# paste_injector.net
KiCad netlist of a schematic drawn in EAGLE
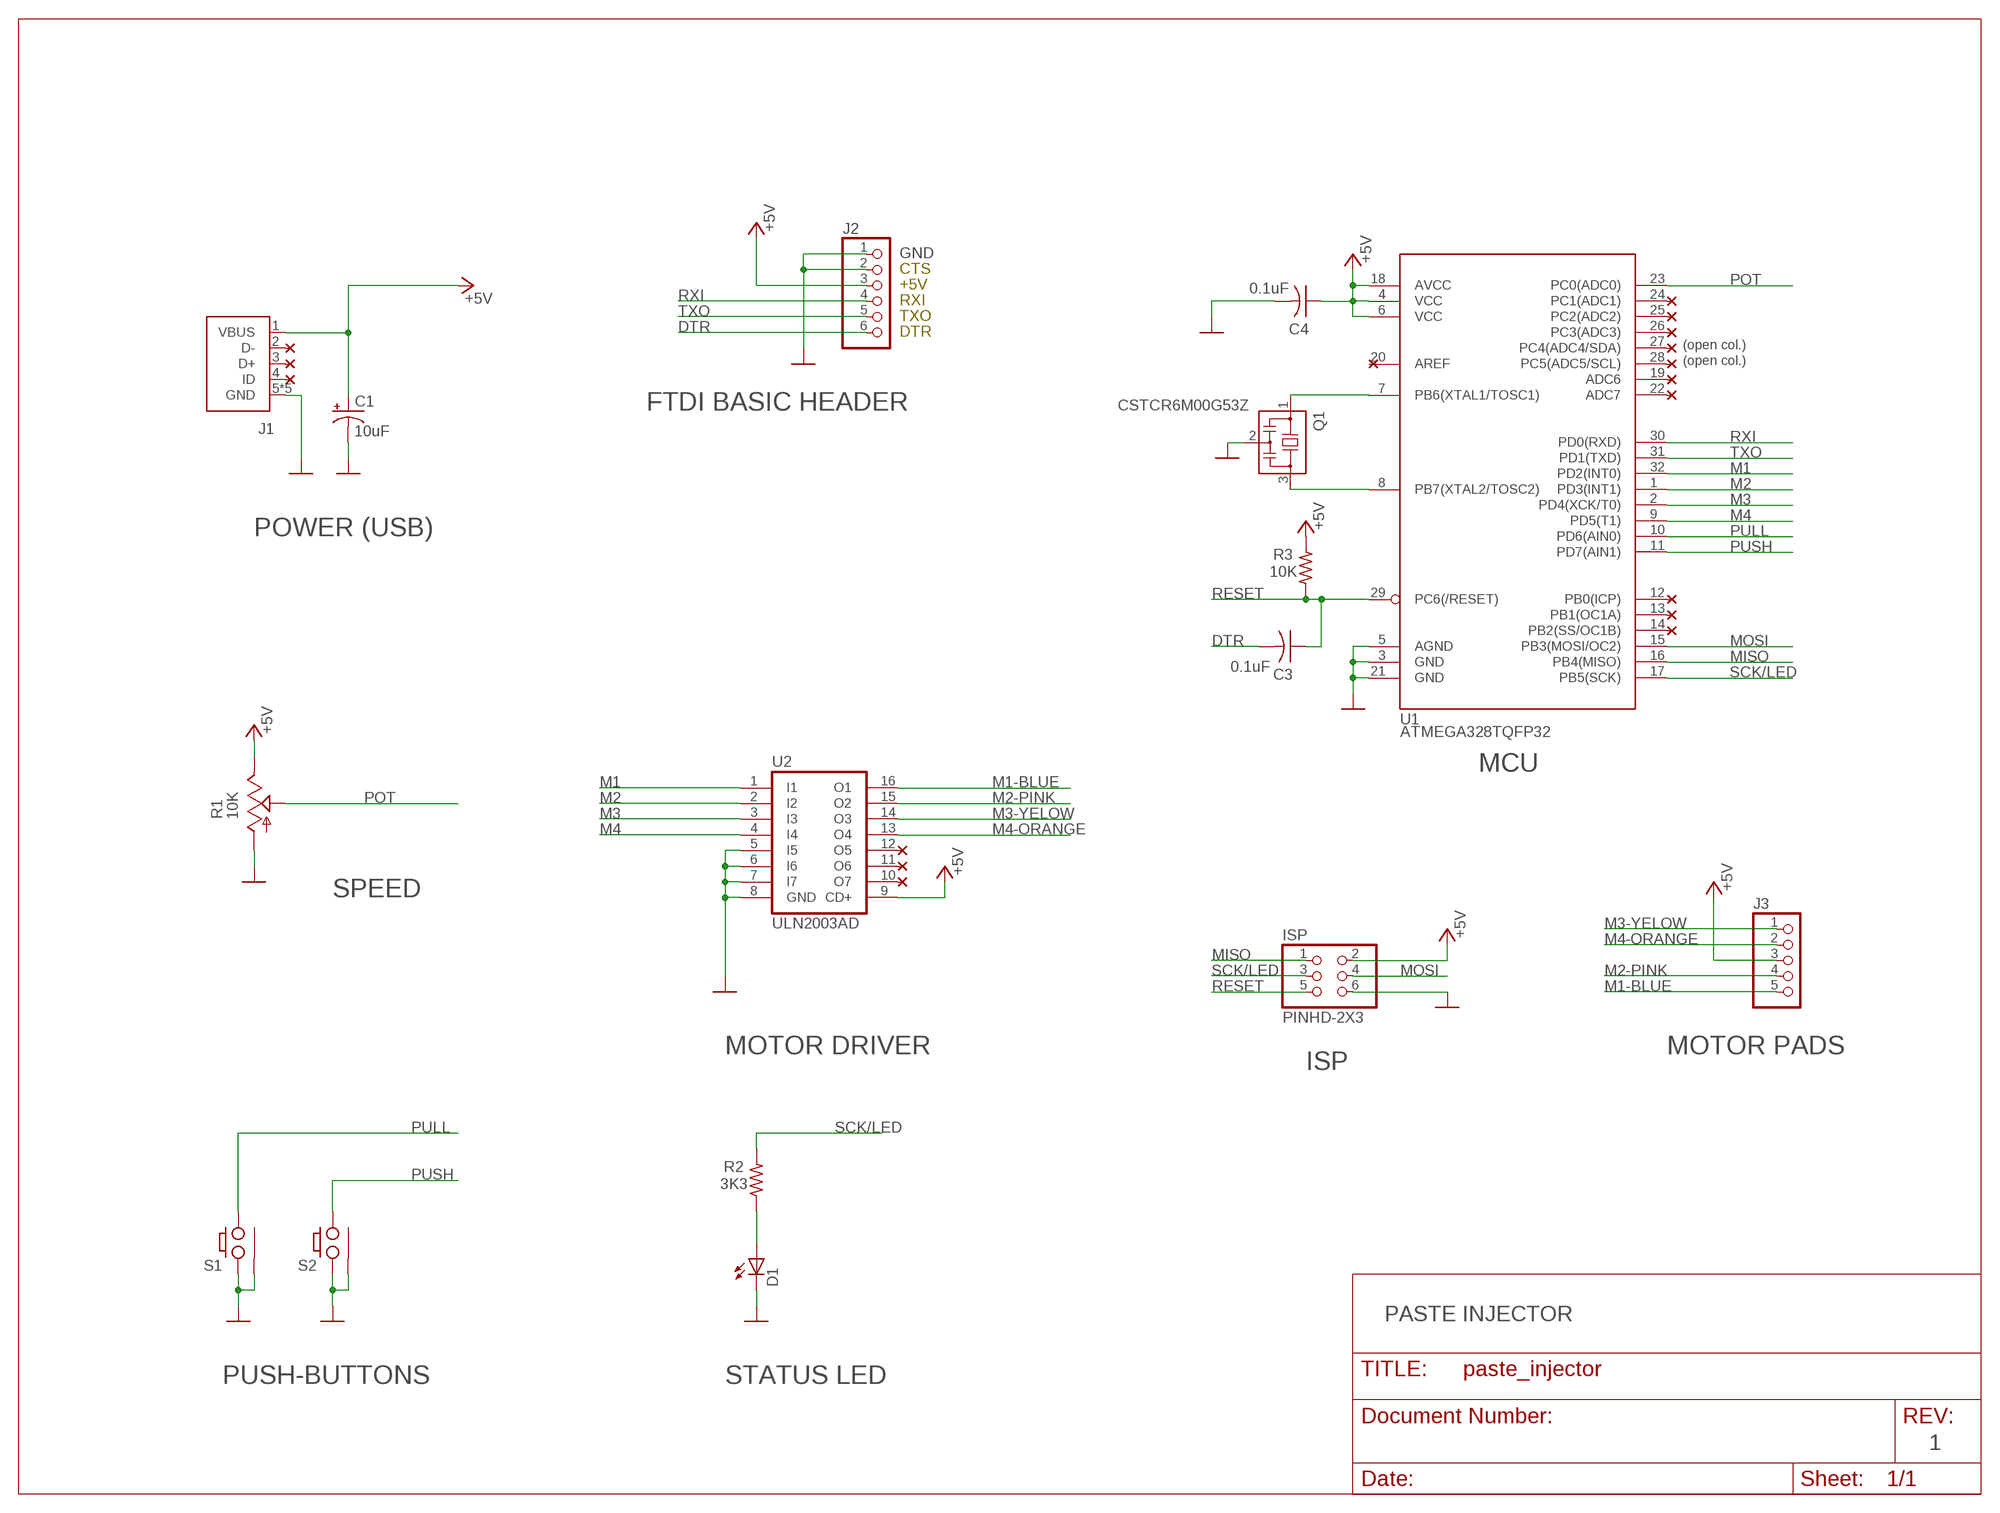
[diagram p0: schematic, sheet 1]

(export (version "E")
  (design (tool "Eeschema 10.0.6"))
  (components
    (comp (ref "C1")
      (value "10uF")
      (footprint "eagle-import:A_3216-18R")
      (libsource (lib "eagle-import") (part "CPOL-USA/3216-18R"))
    )
    (comp (ref "C3")
      (value "0.1uF")
      (footprint "eagle-import:C0603")
      (libsource (lib "eagle-import") (part "CAP-C0603"))
    )
    (comp (ref "C4")
      (value "0.1uF")
      (footprint "eagle-import:C0603")
      (libsource (lib "eagle-import") (part "CAP-C0603"))
    )
    (comp (ref "D1")
      (value "LED")
      (footprint "eagle-import:LED0603")
      (libsource (lib "eagle-import") (part "LED"))
    )
    (comp (ref "ISP")
      (value "PINHD-2X3")
      (footprint "eagle-import:2X03")
      (libsource (lib "eagle-import") (part "PINHD-2X3"))
    )
    (comp (ref "J1")
      (value "USB")
      (footprint "eagle-import:USB-MICRO-ZX62RD-AB-5P8")
      (libsource (lib "eagle-import") (part "USB"))
    )
    (comp (ref "J2")
      (value "PINHD-1X6")
      (footprint "eagle-import:1X06")
      (libsource (lib "eagle-import") (part "PINHD-1X6"))
    )
    (comp (ref "J3")
      (value "PINHD-1X5")
      (footprint "eagle-import:1X05")
      (libsource (lib "eagle-import") (part "PINHD-1X5"))
    )
    (comp (ref "Q1")
      (value "CSTCR6M00G53Z")
      (footprint "eagle-import:CSTCR6M")
      (fields (field (name "MPN") "CSTCR6M00G53-R0"))
      (libsource (lib "eagle-import") (part "CSTCR6M00G53Z"))
    )
    (comp (ref "R1")
      (value "10K")
      (footprint "eagle-import:TRIMPOT")
      (libsource (lib "eagle-import") (part "TRIMPOTCA9V"))
    )
    (comp (ref "R2")
      (value "3K3")
      (footprint "eagle-import:R0603")
      (libsource (lib "eagle-import") (part "RES-R0603"))
    )
    (comp (ref "R3")
      (value "10K")
      (footprint "eagle-import:R0603")
      (libsource (lib "eagle-import") (part "RES-R0603"))
    )
    (comp (ref "S1")
      (value "PUSH_BUTTON")
      (footprint "eagle-import:PUSH_BUTTON")
      (libsource (lib "eagle-import") (part "PUSH_BUTTON"))
    )
    (comp (ref "S2")
      (value "PUSH_BUTTON")
      (footprint "eagle-import:PUSH_BUTTON")
      (libsource (lib "eagle-import") (part "PUSH_BUTTON"))
    )
    (comp (ref "U1")
      (value "ATMEGA328TQFP32")
      (footprint "eagle-import:TQFP32-08")
      (libsource (lib "eagle-import") (part "ATMEGA328TQFP32"))
    )
    (comp (ref "U2")
      (value "ULN2003AD")
      (footprint "eagle-import:SO16")
      (libsource (lib "eagle-import") (part "ULN2003AD"))
    )
  )
  (nets
    (net (code "1") (name "+5V") (class "Default")
      (node (ref "C1") (pin "+") (pinfunction "+_+") (pintype "passive"))
      (node (ref "C4") (pin "1") (pinfunction "1_1") (pintype "passive"))
      (node (ref "ISP") (pin "2") (pinfunction "2_2") (pintype "passive"))
      (node (ref "J1") (pin "1") (pinfunction "VBUS_1") (pintype "bidirectional"))
      (node (ref "J2") (pin "3") (pinfunction "3_3") (pintype "passive"))
      (node (ref "J3") (pin "3") (pinfunction "3_3") (pintype "passive"))
      (node (ref "R1") (pin "CW") (pinfunction "CW_CW") (pintype "passive"))
      (node (ref "R3") (pin "2") (pinfunction "2_2") (pintype "passive"))
      (node (ref "U1") (pin "18") (pinfunction "AVCC_18") (pintype "power_in"))
      (node (ref "U1") (pin "4") (pinfunction "VCC_4") (pintype "power_in"))
      (node (ref "U1") (pin "6") (pinfunction "VCC_6") (pintype "power_in"))
      (node (ref "U2") (pin "9") (pinfunction "CD+_9") (pintype "passive"))
    )
    (net (code "2") (name "/AREF") (class "Default")
      (node (ref "U1") (pin "20") (pinfunction "AREF_20") (pintype "power_in"))
    )
    (net (code "3") (name "/DTR") (class "Default")
      (node (ref "C3") (pin "2") (pinfunction "2_2") (pintype "passive"))
      (node (ref "J2") (pin "6") (pinfunction "6_6") (pintype "passive"))
    )
    (net (code "4") (name "/M1") (class "Default")
      (node (ref "U1") (pin "32") (pinfunction "PD2(INT0)_32") (pintype "bidirectional"))
      (node (ref "U2") (pin "1") (pinfunction "I1_1") (pintype "input"))
    )
    (net (code "5") (name "/M1-BLUE") (class "Default")
      (node (ref "J3") (pin "5") (pinfunction "5_5") (pintype "passive"))
      (node (ref "U2") (pin "16") (pinfunction "O1_16") (pintype "open_collector"))
    )
    (net (code "6") (name "/M2") (class "Default")
      (node (ref "U1") (pin "1") (pinfunction "PD3(INT1)_1") (pintype "bidirectional"))
      (node (ref "U2") (pin "2") (pinfunction "I2_2") (pintype "input"))
    )
    (net (code "7") (name "/M2-PINK") (class "Default")
      (node (ref "J3") (pin "4") (pinfunction "4_4") (pintype "passive"))
      (node (ref "U2") (pin "15") (pinfunction "O2_15") (pintype "open_collector"))
    )
    (net (code "8") (name "/M3") (class "Default")
      (node (ref "U1") (pin "2") (pinfunction "PD4(XCK/T0)_2") (pintype "bidirectional"))
      (node (ref "U2") (pin "3") (pinfunction "I3_3") (pintype "input"))
    )
    (net (code "9") (name "/M3-YELOW") (class "Default")
      (node (ref "J3") (pin "1") (pinfunction "1_1") (pintype "passive"))
      (node (ref "U2") (pin "14") (pinfunction "O3_14") (pintype "open_collector"))
    )
    (net (code "10") (name "/M4") (class "Default")
      (node (ref "U1") (pin "9") (pinfunction "PD5(T1)_9") (pintype "bidirectional"))
      (node (ref "U2") (pin "4") (pinfunction "I4_4") (pintype "input"))
    )
    (net (code "11") (name "/M4-ORANGE") (class "Default")
      (node (ref "J3") (pin "2") (pinfunction "2_2") (pintype "passive"))
      (node (ref "U2") (pin "13") (pinfunction "O4_13") (pintype "open_collector"))
    )
    (net (code "12") (name "/MISO") (class "Default")
      (node (ref "ISP") (pin "1") (pinfunction "1_1") (pintype "passive"))
      (node (ref "U1") (pin "16") (pinfunction "PB4(MISO)_16") (pintype "bidirectional"))
    )
    (net (code "13") (name "/MOSI") (class "Default")
      (node (ref "ISP") (pin "4") (pinfunction "4_4") (pintype "passive"))
      (node (ref "U1") (pin "15") (pinfunction "PB3(MOSI/OC2)_15") (pintype "bidirectional"))
    )
    (net (code "14") (name "/POT") (class "Default")
      (node (ref "R1") (pin "C") (pinfunction "C_C") (pintype "passive"))
      (node (ref "U1") (pin "23") (pinfunction "PC0(ADC0)_23") (pintype "bidirectional"))
    )
    (net (code "15") (name "/PULL") (class "Default")
      (node (ref "S1") (pin "B1") (pinfunction "2_B1") (pintype "passive"))
      (node (ref "U1") (pin "10") (pinfunction "PD6(AIN0)_10") (pintype "bidirectional"))
    )
    (net (code "16") (name "/PUSH") (class "Default")
      (node (ref "S2") (pin "B1") (pinfunction "2_B1") (pintype "passive"))
      (node (ref "U1") (pin "11") (pinfunction "PD7(AIN1)_11") (pintype "bidirectional"))
    )
    (net (code "17") (name "/RESET") (class "Default")
      (node (ref "C3") (pin "1") (pinfunction "1_1") (pintype "passive"))
      (node (ref "ISP") (pin "5") (pinfunction "5_5") (pintype "passive"))
      (node (ref "R3") (pin "1") (pinfunction "1_1") (pintype "passive"))
      (node (ref "U1") (pin "29") (pinfunction "PC6(/RESET)_29") (pintype "bidirectional"))
    )
    (net (code "18") (name "/RXI") (class "Default")
      (node (ref "J2") (pin "4") (pinfunction "4_4") (pintype "passive"))
      (node (ref "U1") (pin "30") (pinfunction "PD0(RXD)_30") (pintype "bidirectional"))
    )
    (net (code "19") (name "/SCK{slash}LED") (class "Default")
      (node (ref "ISP") (pin "3") (pinfunction "3_3") (pintype "passive"))
      (node (ref "R2") (pin "2") (pinfunction "2_2") (pintype "passive"))
      (node (ref "U1") (pin "17") (pinfunction "PB5(SCK)_17") (pintype "bidirectional"))
    )
    (net (code "20") (name "/TXO") (class "Default")
      (node (ref "J2") (pin "5") (pinfunction "5_5") (pintype "passive"))
      (node (ref "U1") (pin "31") (pinfunction "PD1(TXD)_31") (pintype "bidirectional"))
    )
    (net (code "21") (name "GND") (class "Default")
      (node (ref "C1") (pin "-") (pinfunction "-_-") (pintype "passive"))
      (node (ref "C4") (pin "2") (pinfunction "2_2") (pintype "passive"))
      (node (ref "D1") (pin "C") (pinfunction "C_C") (pintype "passive"))
      (node (ref "ISP") (pin "6") (pinfunction "6_6") (pintype "passive"))
      (node (ref "J1") (pin "5") (pinfunction "GND_5") (pintype "bidirectional"))
      (node (ref "J1") (pin "A") (pinfunction "GND_A") (pintype "bidirectional"))
      (node (ref "J1") (pin "B") (pinfunction "GND_B") (pintype "bidirectional"))
      (node (ref "J1") (pin "C") (pinfunction "GND_C") (pintype "bidirectional"))
      (node (ref "J1") (pin "D") (pinfunction "GND_D") (pintype "bidirectional"))
      (node (ref "J2") (pin "1") (pinfunction "1_1") (pintype "passive"))
      (node (ref "J2") (pin "2") (pinfunction "2_2") (pintype "passive"))
      (node (ref "Q1") (pin "2") (pinfunction "2_2") (pintype "passive"))
      (node (ref "R1") (pin "CCW") (pinfunction "CCW_CCW") (pintype "passive"))
      (node (ref "S1") (pin "A1") (pinfunction "1_A1") (pintype "passive"))
      (node (ref "S1") (pin "GND") (pinfunction "GND_GND") (pintype "power_in"))
      (node (ref "S2") (pin "A1") (pinfunction "1_A1") (pintype "passive"))
      (node (ref "S2") (pin "GND") (pinfunction "GND_GND") (pintype "power_in"))
      (node (ref "U1") (pin "21") (pinfunction "GND_21") (pintype "power_in"))
      (node (ref "U1") (pin "3") (pinfunction "GND_3") (pintype "power_in"))
      (node (ref "U1") (pin "5") (pinfunction "AGND_5") (pintype "power_in"))
      (node (ref "U2") (pin "5") (pinfunction "I5_5") (pintype "input"))
      (node (ref "U2") (pin "6") (pinfunction "I6_6") (pintype "input"))
      (node (ref "U2") (pin "7") (pinfunction "I7_7") (pintype "input"))
      (node (ref "U2") (pin "8") (pinfunction "GND_8") (pintype "power_in"))
    )
    (net (code "22") (name "Net-(D1-PadA)") (class "Default")
      (node (ref "D1") (pin "A") (pinfunction "A_A") (pintype "passive"))
      (node (ref "R2") (pin "1") (pinfunction "1_1") (pintype "passive"))
    )
    (net (code "23") (name "Net-(U1-PB6(XTAL1{slash}TOSC1))") (class "Default")
      (node (ref "Q1") (pin "1") (pinfunction "1_1") (pintype "passive"))
      (node (ref "U1") (pin "7") (pinfunction "PB6(XTAL1/TOSC1)_7") (pintype "bidirectional"))
    )
    (net (code "24") (name "Net-(U1-PB7(XTAL2{slash}TOSC2))") (class "Default")
      (node (ref "Q1") (pin "3") (pinfunction "3_3") (pintype "passive"))
      (node (ref "U1") (pin "8") (pinfunction "PB7(XTAL2/TOSC2)_8") (pintype "bidirectional"))
    )
    (net (code "25") (name "unconnected-(J1-D+-Pad3)") (class "Default")
      (node (ref "J1") (pin "3") (pinfunction "D+_3") (pintype "bidirectional"))
    )
    (net (code "26") (name "unconnected-(J1-D--Pad2)") (class "Default")
      (node (ref "J1") (pin "2") (pinfunction "D-_2") (pintype "bidirectional"))
    )
    (net (code "27") (name "unconnected-(J1-ID-Pad4)") (class "Default")
      (node (ref "J1") (pin "4") (pinfunction "ID_4") (pintype "bidirectional"))
    )
    (net (code "28") (name "unconnected-(U1-ADC6-Pad19)") (class "Default")
      (node (ref "U1") (pin "19") (pinfunction "ADC6_19") (pintype "bidirectional"))
    )
    (net (code "29") (name "unconnected-(U1-ADC7-Pad22)") (class "Default")
      (node (ref "U1") (pin "22") (pinfunction "ADC7_22") (pintype "bidirectional"))
    )
    (net (code "30") (name "unconnected-(U1-PB0(ICP)-Pad12)") (class "Default")
      (node (ref "U1") (pin "12") (pinfunction "PB0(ICP)_12") (pintype "bidirectional"))
    )
    (net (code "31") (name "unconnected-(U1-PB1(OC1A)-Pad13)") (class "Default")
      (node (ref "U1") (pin "13") (pinfunction "PB1(OC1A)_13") (pintype "bidirectional"))
    )
    (net (code "32") (name "unconnected-(U1-PB2(SS{slash}OC1B)-Pad14)") (class "Default")
      (node (ref "U1") (pin "14") (pinfunction "PB2(SS/OC1B)_14") (pintype "bidirectional"))
    )
    (net (code "33") (name "unconnected-(U1-PC1(ADC1)-Pad24)") (class "Default")
      (node (ref "U1") (pin "24") (pinfunction "PC1(ADC1)_24") (pintype "bidirectional"))
    )
    (net (code "34") (name "unconnected-(U1-PC2(ADC2)-Pad25)") (class "Default")
      (node (ref "U1") (pin "25") (pinfunction "PC2(ADC2)_25") (pintype "bidirectional"))
    )
    (net (code "35") (name "unconnected-(U1-PC3(ADC3)-Pad26)") (class "Default")
      (node (ref "U1") (pin "26") (pinfunction "PC3(ADC3)_26") (pintype "bidirectional"))
    )
    (net (code "36") (name "unconnected-(U1-PC4(ADC4{slash}SDA)-Pad27)") (class "Default")
      (node (ref "U1") (pin "27") (pinfunction "PC4(ADC4/SDA)_27") (pintype "bidirectional"))
    )
    (net (code "37") (name "unconnected-(U1-PC5(ADC5{slash}SCL)-Pad28)") (class "Default")
      (node (ref "U1") (pin "28") (pinfunction "PC5(ADC5/SCL)_28") (pintype "bidirectional"))
    )
    (net (code "38") (name "unconnected-(U2-O5-Pad12)") (class "Default")
      (node (ref "U2") (pin "12") (pinfunction "O5_12") (pintype "open_collector"))
    )
    (net (code "39") (name "unconnected-(U2-O6-Pad11)") (class "Default")
      (node (ref "U2") (pin "11") (pinfunction "O6_11") (pintype "open_collector"))
    )
    (net (code "40") (name "unconnected-(U2-O7-Pad10)") (class "Default")
      (node (ref "U2") (pin "10") (pinfunction "O7_10") (pintype "open_collector"))
    )
  )
)
